# microcontroller.net
KiCad netlist of a schematic drawn in Altium Designer
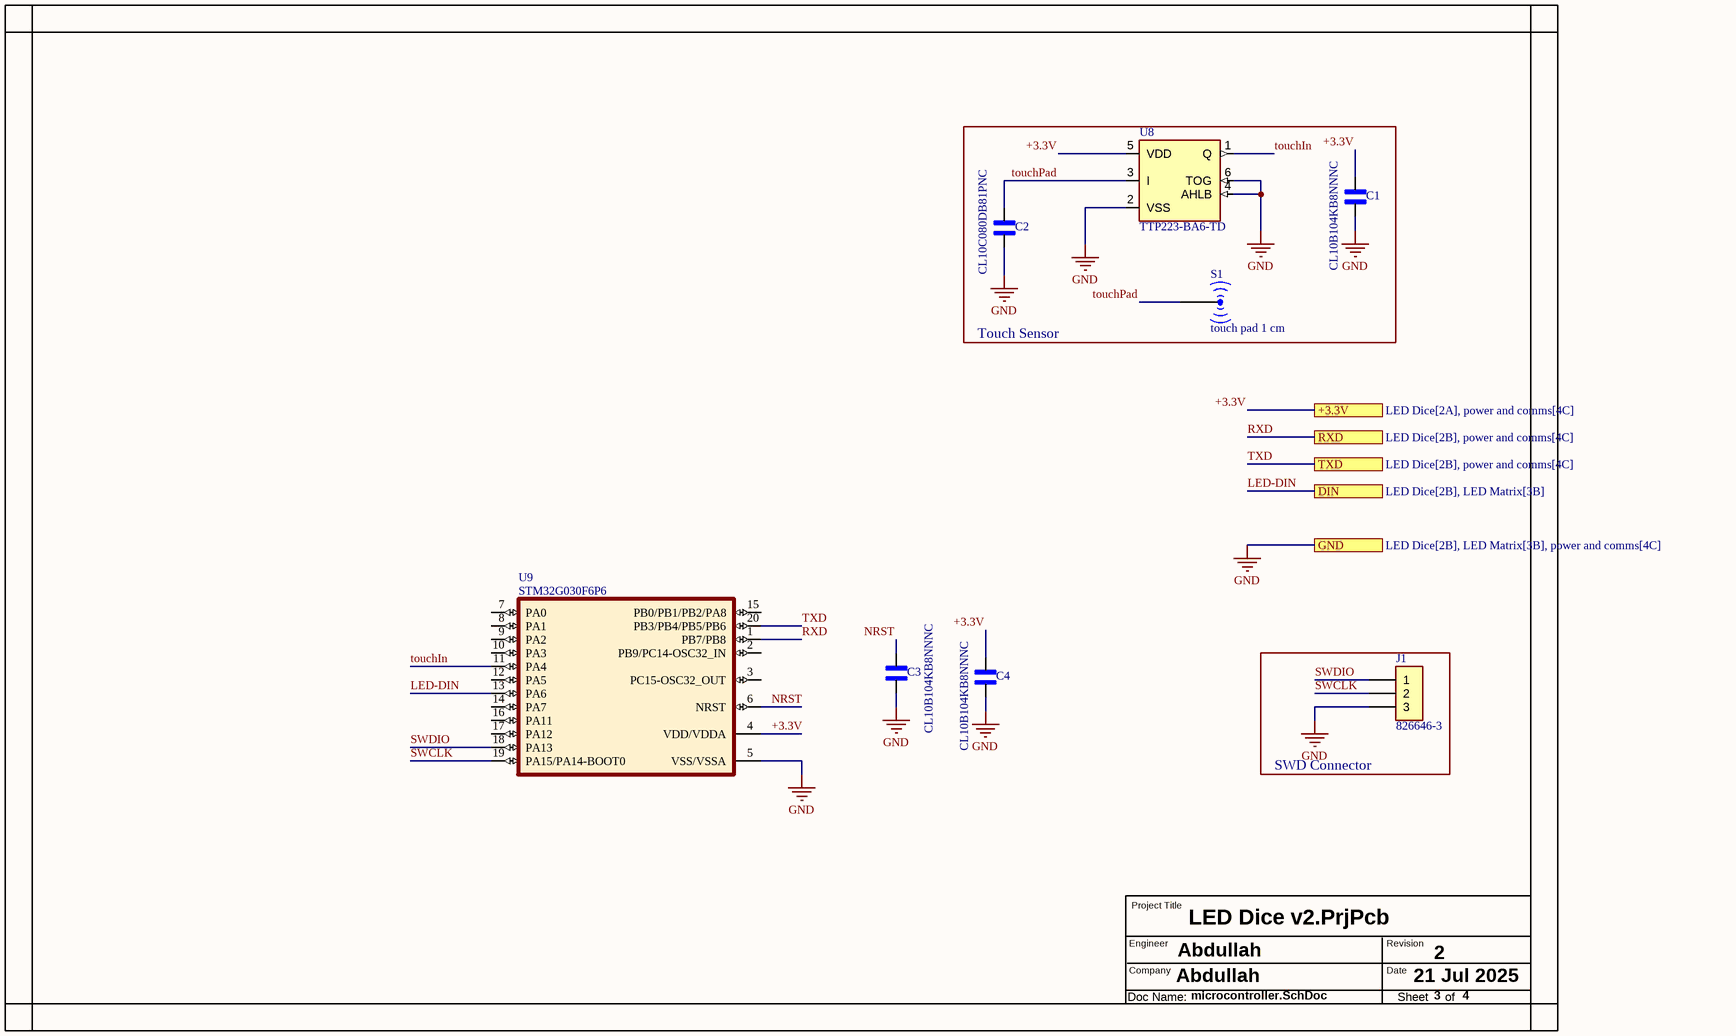
[diagram p0: microcontroller.SchDoc]

(export (version "E")
  (design (tool "Eeschema 10.0.6"))
  (components
    (comp (ref "C1")
      (value "CL10B104KB8NNNC")
      (footprint "CAPC1608X90N")
      (description "0.1ÂµF Â±10% 50V Ceramic Capacitor X7R 0603 _1608 Metric_")
      (fields (field (name "MF") "Samsung Electro-Mechanics"))
      (libsource (lib "Cap 0603 MLCC") (part "CL10B104KB8NNNC"))
    )
    (comp (ref "C2")
      (value "CL10C080DB81PNC")
      (footprint "CAPC1608X90N")
      (description "50V 8pF C0G 0603 Multilayer Ceramic Capacitors MLCC - SMD/SMT ROHS")
      (fields (field (name "MP") "GRM0335C1E8R0CA01D"))
      (libsource (lib "Cap 0603 MLCC") (part "CL10C080DB81PNC"))
    )
    (comp (ref "C3")
      (value "CL10B104KB8NNNC")
      (footprint "CAPC1608X90N")
      (description "0.1ÂµF Â±10% 50V Ceramic Capacitor X7R 0603 _1608 Metric_")
      (fields (field (name "MF") "Samsung Electro-Mechanics"))
      (libsource (lib "Cap 0603 MLCC") (part "CL10B104KB8NNNC"))
    )
    (comp (ref "C4")
      (value "CL10B104KB8NNNC")
      (footprint "CAPC1608X90N")
      (description "0.1ÂµF Â±10% 50V Ceramic Capacitor X7R 0603 _1608 Metric_")
      (fields (field (name "MF") "Samsung Electro-Mechanics"))
      (libsource (lib "Cap 0603 MLCC") (part "CL10B104KB8NNNC"))
    )
    (comp (ref "J1")
      (value "826646-3")
      (footprint "TE_826646-3")
      (description "Connector Header Through Hole 3 position 0.100 (2.54mm)")
      (fields (field (name "MF") "TE Connectivity"))
      (libsource (lib "826646-3") (part "826646-3"))
    )
    (comp (ref "S1")
      (value "touch pad 1 cm")
      (footprint "touch pad 1 cm")
      (description "Touch pad circular 1 cm")
      (libsource (lib "touch pads") (part "touch pad 1 cm"))
    )
    (comp (ref "U8")
      (value "TTP223-BA6-TD")
      (footprint "SOT23-6")
      (description "1 key touchpad detector IC")
      (fields (field (name "MF") "tontek") (field (name "MP") "TTP223-BA6"))
      (libsource (lib "TTP223-BA6") (part "TTP223-BA6-TD"))
    )
    (comp (ref "U9")
      (value "STM32G030F6P6")
      (footprint "*TSSOP20")
      (description "ARMÂ® CortexÂ®-M0+ STM32G0 Microcontroller IC 32-Bit Single-Core 64MHz 32KB (32K x 8) FLASH 20-TSSOP")
      (fields (field (name "MF") "STMicroelectronics"))
      (libsource (lib "STM32G030F6P6") (part "STM32G030F6P6"))
    )
  )
  (nets
    (net (code "1") (name "/+3.3V") (class "Default")
      (node (ref "C1") (pin "2") (pinfunction "2_2") (pintype "passive"))
      (node (ref "C4") (pin "2") (pinfunction "2_2") (pintype "passive"))
      (node (ref "U8") (pin "5") (pinfunction "VDD_5") (pintype "power_in"))
      (node (ref "U9") (pin "4") (pinfunction "VDD/VDDA_4") (pintype "power_in"))
    )
    (net (code "2") (name "/LED-DIN") (class "Default")
      (node (ref "U9") (pin "13") (pinfunction "PA6_13") (pintype "bidirectional"))
    )
    (net (code "3") (name "/NRST") (class "Default")
      (node (ref "C3") (pin "2") (pinfunction "2_2") (pintype "passive"))
      (node (ref "U9") (pin "6") (pinfunction "NRST_6") (pintype "bidirectional"))
    )
    (net (code "4") (name "/RXD") (class "Default")
      (node (ref "U9") (pin "1") (pinfunction "PB7/PB8_1") (pintype "bidirectional"))
    )
    (net (code "5") (name "/SWCLK") (class "Default")
      (node (ref "J1") (pin "2") (pinfunction "2_2") (pintype "passive"))
      (node (ref "U9") (pin "19") (pinfunction "PA15/PA14-BOOT0_19") (pintype "bidirectional"))
    )
    (net (code "6") (name "/SWDIO") (class "Default")
      (node (ref "J1") (pin "1") (pinfunction "1_1") (pintype "passive"))
      (node (ref "U9") (pin "18") (pinfunction "PA13_18") (pintype "bidirectional"))
    )
    (net (code "7") (name "/TXD") (class "Default")
      (node (ref "U9") (pin "20") (pinfunction "PB3/PB4/PB5/PB6_20") (pintype "bidirectional"))
    )
    (net (code "8") (name "/touchIn") (class "Default")
      (node (ref "U8") (pin "1") (pinfunction "Q_1") (pintype "output"))
      (node (ref "U9") (pin "11") (pinfunction "PA4_11") (pintype "bidirectional"))
    )
    (net (code "9") (name "/touchPad") (class "Default")
      (node (ref "C2") (pin "2") (pinfunction "2_2") (pintype "passive"))
      (node (ref "S1") (pin "1") (pinfunction "in_1") (pintype "passive"))
      (node (ref "U8") (pin "3") (pinfunction "I_3") (pintype "bidirectional"))
    )
    (net (code "10") (name "GND") (class "Default")
      (node (ref "C1") (pin "1") (pinfunction "1_1") (pintype "passive"))
      (node (ref "C2") (pin "1") (pinfunction "1_1") (pintype "passive"))
      (node (ref "C3") (pin "1") (pinfunction "1_1") (pintype "passive"))
      (node (ref "C4") (pin "1") (pinfunction "1_1") (pintype "passive"))
      (node (ref "J1") (pin "3") (pinfunction "3_3") (pintype "passive"))
      (node (ref "U8") (pin "2") (pinfunction "VSS_2") (pintype "power_in"))
      (node (ref "U8") (pin "4") (pinfunction "AHLB_4") (pintype "input"))
      (node (ref "U8") (pin "6") (pinfunction "TOG_6") (pintype "input"))
      (node (ref "U9") (pin "5") (pinfunction "VSS/VSSA_5") (pintype "power_in"))
    )
    (net (code "11") (name "unconnected-(U9-PA0-Pad7)") (class "Default")
      (node (ref "U9") (pin "7") (pinfunction "PA0_7") (pintype "bidirectional"))
    )
    (net (code "12") (name "unconnected-(U9-PA1-Pad8)") (class "Default")
      (node (ref "U9") (pin "8") (pinfunction "PA1_8") (pintype "bidirectional"))
    )
    (net (code "13") (name "unconnected-(U9-PA2-Pad9)") (class "Default")
      (node (ref "U9") (pin "9") (pinfunction "PA2_9") (pintype "bidirectional"))
    )
    (net (code "14") (name "unconnected-(U9-PA3-Pad10)") (class "Default")
      (node (ref "U9") (pin "10") (pinfunction "PA3_10") (pintype "bidirectional"))
    )
    (net (code "15") (name "unconnected-(U9-PA5-Pad12)") (class "Default")
      (node (ref "U9") (pin "12") (pinfunction "PA5_12") (pintype "bidirectional"))
    )
    (net (code "16") (name "unconnected-(U9-PA7-Pad14)") (class "Default")
      (node (ref "U9") (pin "14") (pinfunction "PA7_14") (pintype "bidirectional"))
    )
    (net (code "17") (name "unconnected-(U9-PA11-Pad16)") (class "Default")
      (node (ref "U9") (pin "16") (pinfunction "PA11_16") (pintype "bidirectional"))
    )
    (net (code "18") (name "unconnected-(U9-PA12-Pad17)") (class "Default")
      (node (ref "U9") (pin "17") (pinfunction "PA12_17") (pintype "bidirectional"))
    )
    (net (code "19") (name "unconnected-(U9-PB0{slash}PB1{slash}PB2{slash}PA8-Pad15)") (class "Default")
      (node (ref "U9") (pin "15") (pinfunction "PB0/PB1/PB2/PA8_15") (pintype "bidirectional"))
    )
    (net (code "20") (name "unconnected-(U9-PB9{slash}PC14-OSC32_IN-Pad2)") (class "Default")
      (node (ref "U9") (pin "2") (pinfunction "PB9/PC14-OSC32_IN_2") (pintype "bidirectional"))
    )
    (net (code "21") (name "unconnected-(U9-PC15-OSC32_OUT-Pad3)") (class "Default")
      (node (ref "U9") (pin "3") (pinfunction "PC15-OSC32_OUT_3") (pintype "bidirectional"))
    )
  )
)
